# TF_CARD_USB.net
KiCad netlist of a schematic drawn in Altium Designer
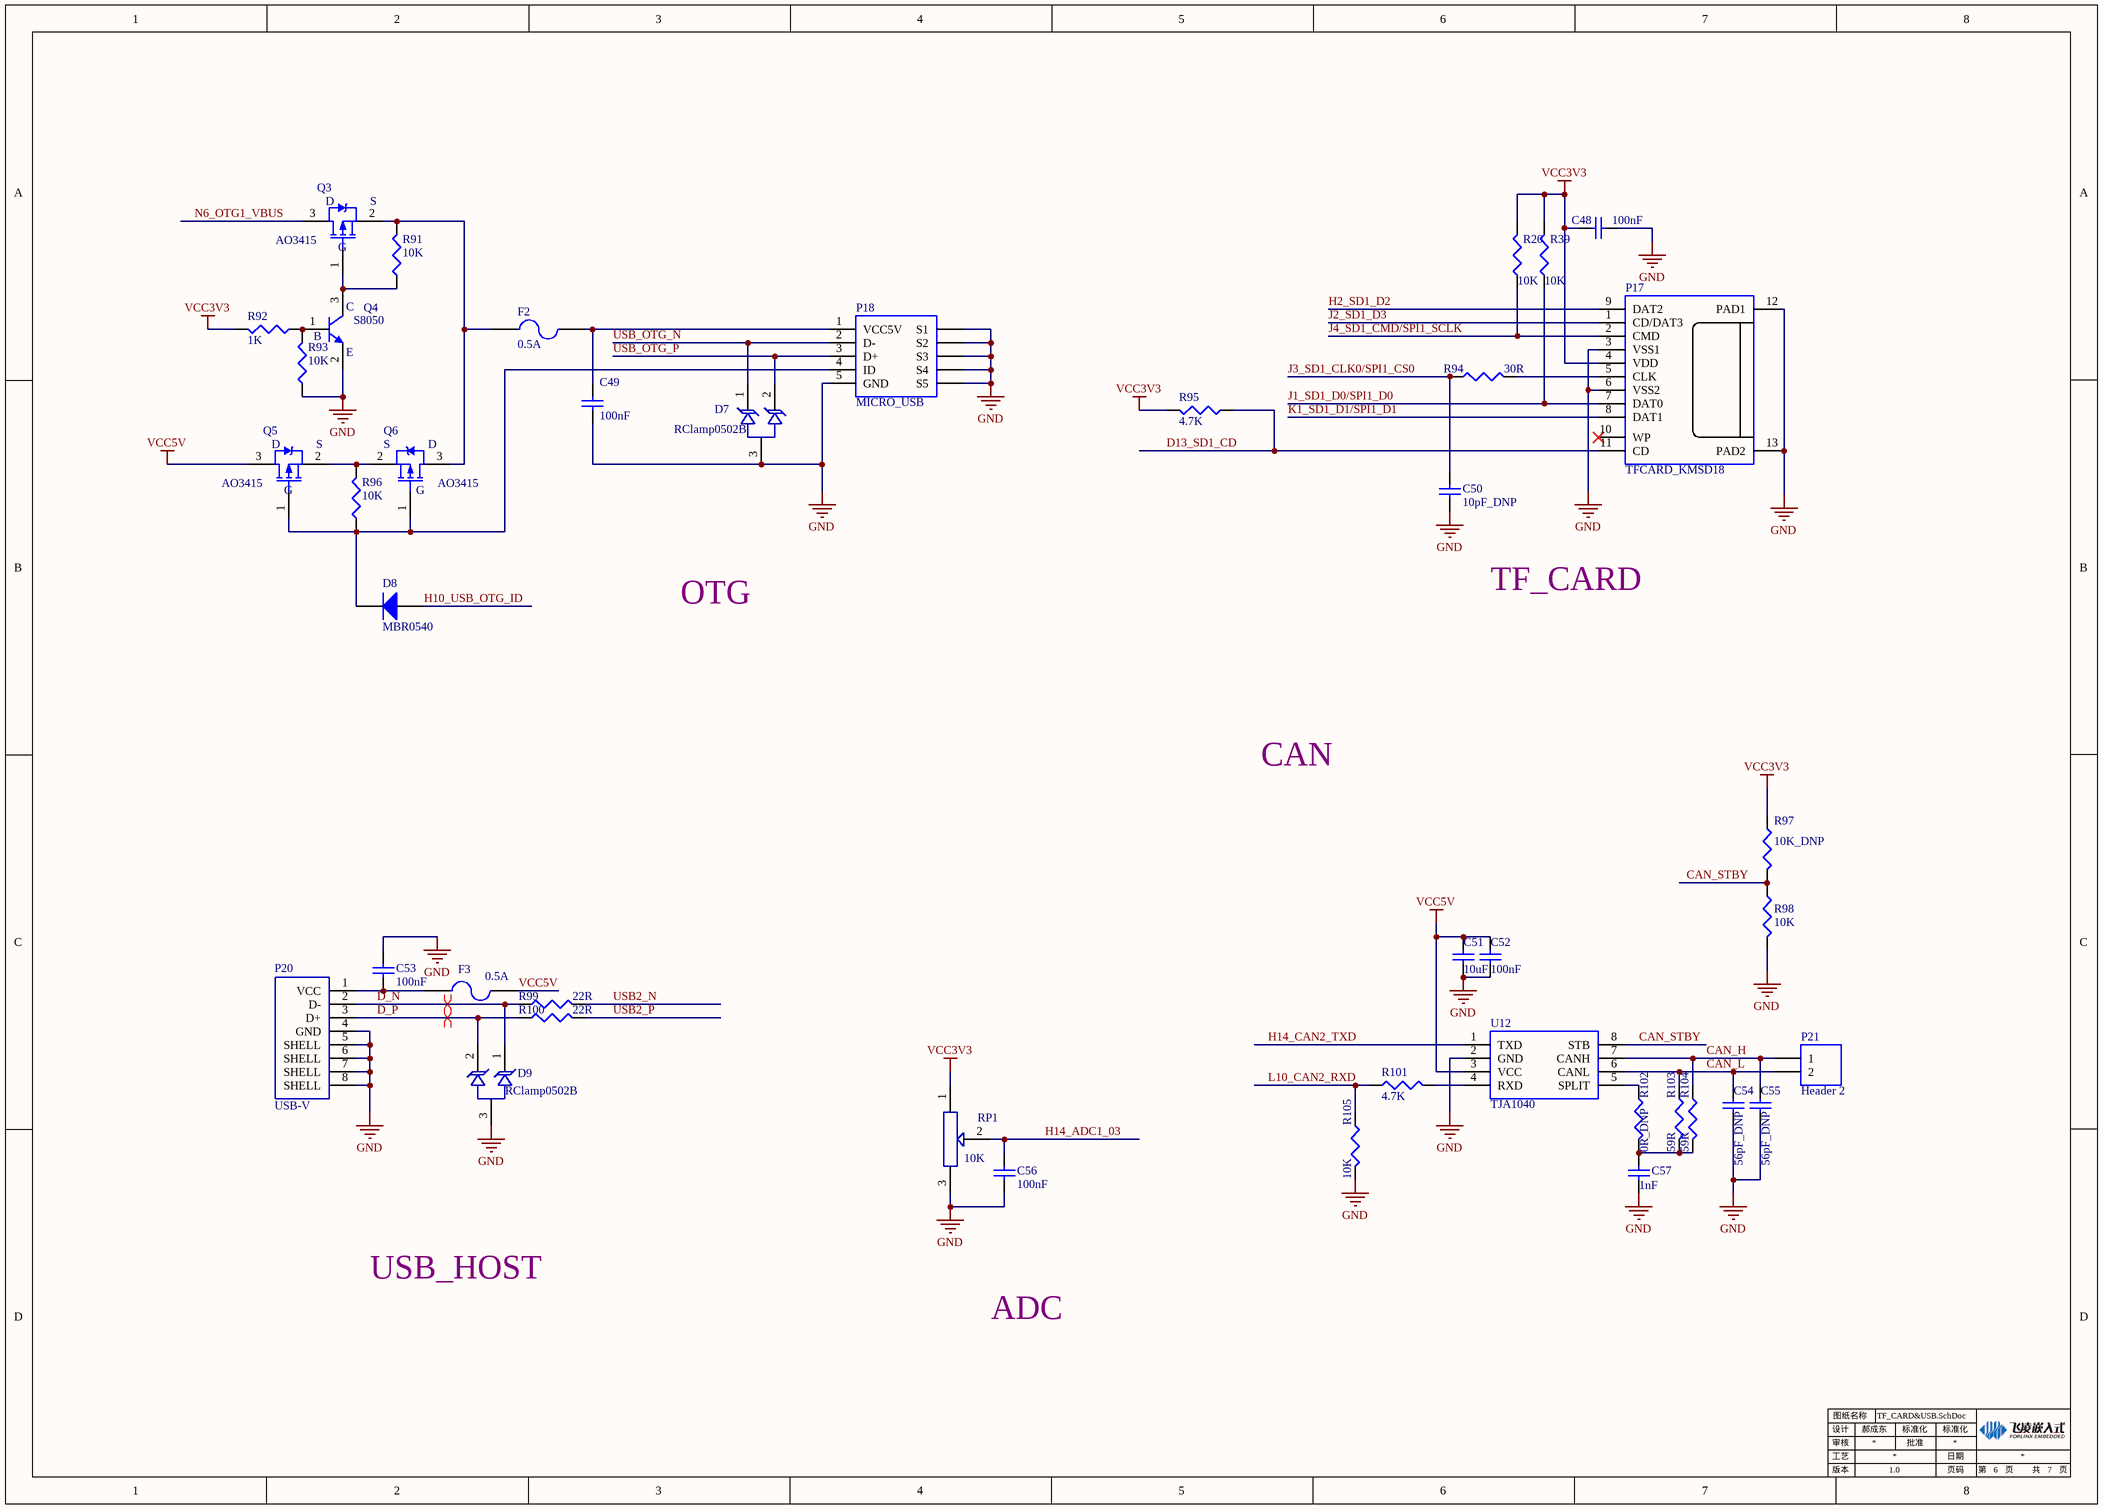
[diagram p0: TF_CARD&USB.SchDoc]

(export (version "E")
  (design (tool "Eeschema 10.0.6"))
  (components
    (comp (ref "C48")
      (value "100nF")
      (footprint "0603C+")
      (description "Capacitor")
      (fields (field (name "PUBLISHER") "Altium Limited"))
      (libsource (lib "Miscellaneous Devices") (part "Cap"))
    )
    (comp (ref "C49")
      (value "100nF")
      (footprint "0603C+")
      (description "Capacitor")
      (fields (field (name "PUBLISHER") "Altium Limited"))
      (libsource (lib "Miscellaneous Devices") (part "Cap"))
    )
    (comp (ref "C50")
      (value "10pF_DNP")
      (footprint "0603C+")
      (description "Capacitor")
      (fields (field (name "PUBLISHER") "Altium Limited"))
      (libsource (lib "Miscellaneous Devices") (part "Cap"))
    )
    (comp (ref "C51")
      (value "10uF")
      (footprint "0603C+")
      (description "Capacitor")
      (fields (field (name "PUBLISHER") "Altium Limited"))
      (libsource (lib "Miscellaneous Devices") (part "Cap"))
    )
    (comp (ref "C52")
      (value "100nF")
      (footprint "0603C+")
      (description "Capacitor")
      (fields (field (name "PUBLISHER") "Altium Limited"))
      (libsource (lib "Miscellaneous Devices") (part "Cap"))
    )
    (comp (ref "C53")
      (value "100nF")
      (footprint "0603C+")
      (description "Capacitor")
      (fields (field (name "PUBLISHER") "Altium Limited"))
      (libsource (lib "Miscellaneous Devices") (part "Cap"))
    )
    (comp (ref "C54")
      (value "56pF_DNP")
      (footprint "0603C+")
      (description "Capacitor")
      (fields (field (name "PUBLISHER") "Altium Limited"))
      (libsource (lib "Miscellaneous Devices") (part "Cap"))
    )
    (comp (ref "C55")
      (value "56pF_DNP")
      (footprint "0603C+")
      (description "Capacitor")
      (fields (field (name "PUBLISHER") "Altium Limited"))
      (libsource (lib "Miscellaneous Devices") (part "Cap"))
    )
    (comp (ref "C56")
      (value "100nF")
      (footprint "0603C+")
      (description "Capacitor")
      (fields (field (name "PUBLISHER") "Altium Limited"))
      (libsource (lib "Miscellaneous Devices") (part "Cap"))
    )
    (comp (ref "C57")
      (value "1nF")
      (footprint "0603C+")
      (description "Capacitor")
      (fields (field (name "PUBLISHER") "Altium Limited"))
      (libsource (lib "Miscellaneous Devices") (part "Cap"))
    )
    (comp (ref "D7") (value "RClamp0502B") (footprint "SOT-523") (libsource (lib "Sch") (part "LCTVS")))
    (comp (ref "D8")
      (value "MBR0540")
      (footprint "Diode1.6*2.6")
      (description "Default Diode")
      (fields (field (name "PUBLISHER") "Altium Limited"))
      (libsource (lib "Miscellaneous Devices") (part "Diode"))
    )
    (comp (ref "D9") (value "RClamp0502B") (footprint "SOT-523") (libsource (lib "Sch") (part "LCTVS")))
    (comp (ref "F2")
      (value "0.5A")
      (footprint "R_1210")
      (description "Fuse")
      (fields (field (name "PUBLISHER") "Altium Limited"))
      (libsource (lib "Miscellaneous Devices") (part "Fuse 2"))
    )
    (comp (ref "F3")
      (value "0.5A")
      (footprint "R_1210")
      (description "Fuse")
      (fields (field (name "PUBLISHER") "Altium Limited"))
      (libsource (lib "Miscellaneous Devices") (part "Fuse 2"))
    )
    (comp (ref "P17")
      (value "TFCARD_KMSD18")
      (footprint "TF-CARD")
      (libsource (lib "IMX6QP") (part "SDCARD_KMSD18"))
    )
    (comp (ref "P18")
      (value "MICRO_USB")
      (footprint "microUSB")
      (description "Header, 5-Pin, Dual row")
      (fields (field (name "PUBLISHER") "Altium Limited"))
      (libsource (lib "PCB_RT1052") (part "MICRO_USB"))
    )
    (comp (ref "P20") (value "USB-V") (footprint "USB-C") (libsource (lib "IMX6QP-C") (part "USB-V")))
    (comp (ref "P21")
      (value "Header 2")
      (footprint "DG128-2P")
      (libsource (lib "PCB_RT1052") (part "Header 2"))
    )
    (comp (ref "Q3")
      (value "AO3415")
      (footprint "SOT95P245X110-3N")
      (description "N-Channel Power MOSFET")
      (fields (field (name "PUBLISHER") "Altium Limited"))
      (libsource (lib "KQX6A") (part "PMOS"))
    )
    (comp (ref "Q4")
      (value "S8050")
      (footprint "SOT95P245X110-3N")
      (description "NPN Bipolar Transistor")
      (fields (field (name "PUBLISHER") "Altium Limited"))
      (libsource (lib "KQX6A") (part "NPN"))
    )
    (comp (ref "Q5")
      (value "AO3415")
      (footprint "SOT95P245X110-3N")
      (description "N-Channel Power MOSFET")
      (fields (field (name "PUBLISHER") "Altium Limited"))
      (libsource (lib "KQX6A") (part "PMOS"))
    )
    (comp (ref "Q6")
      (value "AO3415")
      (footprint "SOT95P245X110-3N")
      (description "N-Channel Power MOSFET")
      (fields (field (name "PUBLISHER") "Altium Limited"))
      (libsource (lib "KQX6A") (part "PMOS"))
    )
    (comp (ref "R20")
      (value "10K")
      (footprint "0603R+")
      (description "Resistor")
      (fields (field (name "PUBLISHER") "Altium Limited"))
      (libsource (lib "") (part "Res3_1"))
    )
    (comp (ref "R39")
      (value "10K")
      (footprint "0603R+")
      (description "Resistor")
      (fields (field (name "PUBLISHER") "Altium Limited"))
      (libsource (lib "") (part "Res3_1"))
    )
    (comp (ref "R91")
      (value "10K")
      (footprint "0603R+")
      (description "Resistor")
      (fields (field (name "PUBLISHER") "Altium Limited"))
      (libsource (lib "") (part "Res3_1"))
    )
    (comp (ref "R92")
      (value "1K")
      (footprint "0603R+")
      (description "Resistor")
      (fields (field (name "PUBLISHER") "Altium Limited"))
      (libsource (lib "") (part "Res3_1"))
    )
    (comp (ref "R93")
      (value "10K")
      (footprint "0603R+")
      (description "Resistor")
      (fields (field (name "PUBLISHER") "Altium Limited"))
      (libsource (lib "") (part "Res3_1"))
    )
    (comp (ref "R94")
      (value "30R")
      (footprint "0603R+")
      (description "Resistor")
      (fields (field (name "PUBLISHER") "Altium Limited"))
      (libsource (lib "") (part "Res3_1"))
    )
    (comp (ref "R95")
      (value "4.7K")
      (footprint "0603R+")
      (description "Resistor")
      (fields (field (name "PUBLISHER") "Altium Limited"))
      (libsource (lib "") (part "Res3_1"))
    )
    (comp (ref "R96")
      (value "10K")
      (footprint "0603R+")
      (description "Resistor")
      (fields (field (name "PUBLISHER") "Altium Limited"))
      (libsource (lib "") (part "Res3_1"))
    )
    (comp (ref "R97")
      (value "10K_DNP")
      (footprint "0603R+")
      (description "Resistor")
      (fields (field (name "PUBLISHER") "Altium Limited"))
      (libsource (lib "Miscellaneous Devices") (part "Res3"))
    )
    (comp (ref "R98")
      (value "10K")
      (footprint "0603R+")
      (description "Resistor")
      (fields (field (name "PUBLISHER") "Altium Limited"))
      (libsource (lib "Miscellaneous Devices") (part "Res3"))
    )
    (comp (ref "R99")
      (value "22R")
      (footprint "0603R+")
      (description "Resistor")
      (fields (field (name "PUBLISHER") "Altium Limited"))
      (libsource (lib "") (part "Res3_1"))
    )
    (comp (ref "R100")
      (value "22R")
      (footprint "0603R+")
      (description "Resistor")
      (fields (field (name "PUBLISHER") "Altium Limited"))
      (libsource (lib "") (part "Res3_1"))
    )
    (comp (ref "R101")
      (value "4.7K")
      (footprint "0603R+")
      (description "Resistor")
      (fields (field (name "PUBLISHER") "Altium Limited"))
      (libsource (lib "Miscellaneous Devices") (part "Res3"))
    )
    (comp (ref "R102")
      (value "0R_DNP")
      (footprint "0603R+")
      (description "Resistor")
      (fields (field (name "PUBLISHER") "Altium Limited"))
      (libsource (lib "Miscellaneous Devices") (part "Res3"))
    )
    (comp (ref "R103")
      (value "59R")
      (footprint "0603R+")
      (description "Resistor")
      (fields (field (name "PUBLISHER") "Altium Limited"))
      (libsource (lib "Miscellaneous Devices") (part "Res3"))
    )
    (comp (ref "R104")
      (value "59R")
      (footprint "0603R+")
      (description "Resistor")
      (fields (field (name "PUBLISHER") "Altium Limited"))
      (libsource (lib "Miscellaneous Devices") (part "Res3"))
    )
    (comp (ref "R105")
      (value "10K")
      (footprint "0603R+")
      (description "Resistor")
      (fields (field (name "PUBLISHER") "Altium Limited"))
      (libsource (lib "Miscellaneous Devices") (part "Res3"))
    )
    (comp (ref "RP1")
      (value "10K")
      (footprint "3296W")
      (fields (field (name "Comment") "VR-3296W"))
      (libsource (lib "Sch") (part "VR"))
    )
    (comp (ref "U12")
      (value "TJA1040")
      (footprint "SOP127P600X175-8N")
      (libsource (lib "IMX6QP") (part "TJA1040"))
    )
  )
  (nets
    (net (code "1") (name "/CAN_H") (class "Default")
      (node (ref "C55") (pin "1") (pinfunction "1_1") (pintype "passive"))
      (node (ref "P21") (pin "1") (pinfunction "1_1") (pintype "passive"))
      (node (ref "R104") (pin "1") (pinfunction "1_1") (pintype "passive"))
      (node (ref "U12") (pin "7") (pinfunction "CANH_7") (pintype "passive"))
    )
    (net (code "2") (name "/CAN_L") (class "Default")
      (node (ref "C54") (pin "1") (pinfunction "1_1") (pintype "passive"))
      (node (ref "P21") (pin "2") (pinfunction "2_2") (pintype "passive"))
      (node (ref "R103") (pin "1") (pinfunction "1_1") (pintype "passive"))
      (node (ref "U12") (pin "6") (pinfunction "CANL_6") (pintype "passive"))
    )
    (net (code "3") (name "/CAN_STBY") (class "Default")
      (node (ref "R97") (pin "2") (pinfunction "2_2") (pintype "passive"))
      (node (ref "R98") (pin "1") (pinfunction "1_1") (pintype "passive"))
      (node (ref "U12") (pin "8") (pinfunction "STB_8") (pintype "passive"))
    )
    (net (code "4") (name "/D13_SD1_CD") (class "Default")
      (node (ref "P17") (pin "11") (pinfunction "CD_11") (pintype "passive"))
      (node (ref "R95") (pin "1") (pinfunction "1_1") (pintype "passive"))
    )
    (net (code "5") (name "/D_N") (class "Default")
      (node (ref "D9") (pin "1") (pinfunction "1_1") (pintype "passive"))
      (node (ref "P20") (pin "2") (pinfunction "D-_2") (pintype "passive"))
      (node (ref "R99") (pin "1") (pinfunction "1_1") (pintype "passive"))
    )
    (net (code "6") (name "/D_P") (class "Default")
      (node (ref "D9") (pin "2") (pinfunction "2_2") (pintype "passive"))
      (node (ref "P20") (pin "3") (pinfunction "D+_3") (pintype "passive"))
      (node (ref "R100") (pin "1") (pinfunction "1_1") (pintype "passive"))
    )
    (net (code "7") (name "/H2_SD1_D2") (class "Default")
      (node (ref "P17") (pin "9") (pinfunction "DAT2_9") (pintype "passive"))
    )
    (net (code "8") (name "/H10_USB_OTG_ID") (class "Default")
      (node (ref "D8") (pin "1") (pinfunction "A_1") (pintype "passive"))
    )
    (net (code "9") (name "/H14_ADC1_03") (class "Default")
      (node (ref "C56") (pin "2") (pinfunction "2_2") (pintype "passive"))
      (node (ref "RP1") (pin "2") (pinfunction "VCC_2") (pintype "passive"))
    )
    (net (code "10") (name "/H14_CAN2_TXD") (class "Default")
      (node (ref "U12") (pin "1") (pinfunction "TXD_1") (pintype "passive"))
    )
    (net (code "11") (name "/J1_SD1_D0{slash}SPI1_D0") (class "Default")
      (node (ref "P17") (pin "7") (pinfunction "DAT0_7") (pintype "passive"))
      (node (ref "R39") (pin "1") (pinfunction "1_1") (pintype "passive"))
    )
    (net (code "12") (name "/J2_SD1_D3") (class "Default")
      (node (ref "P17") (pin "1") (pinfunction "CD/DAT3_1") (pintype "passive"))
    )
    (net (code "13") (name "/J3_SD1_CLK0{slash}SPI1_CS0") (class "Default")
      (node (ref "C50") (pin "1") (pinfunction "1_1") (pintype "passive"))
      (node (ref "R94") (pin "1") (pinfunction "1_1") (pintype "passive"))
    )
    (net (code "14") (name "/J4_SD1_CMD{slash}SPI1_SCLK") (class "Default")
      (node (ref "P17") (pin "2") (pinfunction "CMD_2") (pintype "passive"))
      (node (ref "R20") (pin "1") (pinfunction "1_1") (pintype "passive"))
    )
    (net (code "15") (name "/K1_SD1_D1{slash}SPI1_D1") (class "Default")
      (node (ref "P17") (pin "8") (pinfunction "DAT1_8") (pintype "passive"))
    )
    (net (code "16") (name "/L10_CAN2_RXD") (class "Default")
      (node (ref "R101") (pin "1") (pinfunction "1_1") (pintype "passive"))
      (node (ref "R105") (pin "1") (pinfunction "1_1") (pintype "passive"))
    )
    (net (code "17") (name "/N6_OTG1_VBUS") (class "Default")
      (node (ref "Q3") (pin "3") (pinfunction "D_3") (pintype "passive"))
    )
    (net (code "18") (name "/USB2_N") (class "Default")
      (node (ref "R99") (pin "2") (pinfunction "2_2") (pintype "passive"))
    )
    (net (code "19") (name "/USB2_P") (class "Default")
      (node (ref "R100") (pin "2") (pinfunction "2_2") (pintype "passive"))
    )
    (net (code "20") (name "/USB_OTG_N") (class "Default")
      (node (ref "D7") (pin "1") (pinfunction "1_1") (pintype "passive"))
      (node (ref "P18") (pin "2") (pinfunction "D-_2") (pintype "passive"))
    )
    (net (code "21") (name "/USB_OTG_P") (class "Default")
      (node (ref "D7") (pin "2") (pinfunction "2_2") (pintype "passive"))
      (node (ref "P18") (pin "3") (pinfunction "D+_3") (pintype "passive"))
    )
    (net (code "22") (name "GND") (class "Default")
      (node (ref "C48") (pin "1") (pinfunction "1_1") (pintype "passive"))
      (node (ref "C49") (pin "1") (pinfunction "1_1") (pintype "passive"))
      (node (ref "C50") (pin "2") (pinfunction "2_2") (pintype "passive"))
      (node (ref "C51") (pin "2") (pinfunction "2_2") (pintype "passive"))
      (node (ref "C52") (pin "2") (pinfunction "2_2") (pintype "passive"))
      (node (ref "C53") (pin "1") (pinfunction "1_1") (pintype "passive"))
      (node (ref "C54") (pin "2") (pinfunction "2_2") (pintype "passive"))
      (node (ref "C55") (pin "2") (pinfunction "2_2") (pintype "passive"))
      (node (ref "C56") (pin "1") (pinfunction "1_1") (pintype "passive"))
      (node (ref "C57") (pin "2") (pinfunction "2_2") (pintype "passive"))
      (node (ref "D7") (pin "3") (pintype "passive"))
      (node (ref "D9") (pin "3") (pintype "passive"))
      (node (ref "P17") (pin "12") (pinfunction "PAD1_12") (pintype "passive"))
      (node (ref "P17") (pin "13") (pinfunction "PAD2_13") (pintype "passive"))
      (node (ref "P17") (pin "3") (pinfunction "VSS1_3") (pintype "passive"))
      (node (ref "P17") (pin "6") (pinfunction "VSS2_6") (pintype "passive"))
      (node (ref "P18") (pin "10") (pinfunction "S5_10") (pintype "passive"))
      (node (ref "P18") (pin "5") (pinfunction "GND_5") (pintype "passive"))
      (node (ref "P18") (pin "6") (pinfunction "S1_6") (pintype "passive"))
      (node (ref "P18") (pin "7") (pinfunction "S2_7") (pintype "passive"))
      (node (ref "P18") (pin "8") (pinfunction "S3_8") (pintype "passive"))
      (node (ref "P18") (pin "9") (pinfunction "S4_9") (pintype "passive"))
      (node (ref "P20") (pin "4") (pinfunction "GND_4") (pintype "passive"))
      (node (ref "P20") (pin "5") (pinfunction "SHELL_5") (pintype "passive"))
      (node (ref "P20") (pin "6") (pinfunction "SHELL_6") (pintype "passive"))
      (node (ref "P20") (pin "7") (pinfunction "SHELL_7") (pintype "passive"))
      (node (ref "P20") (pin "8") (pinfunction "SHELL_8") (pintype "passive"))
      (node (ref "Q4") (pin "2") (pinfunction "E_2") (pintype "passive"))
      (node (ref "R105") (pin "2") (pinfunction "2_2") (pintype "passive"))
      (node (ref "R93") (pin "1") (pinfunction "1_1") (pintype "passive"))
      (node (ref "R98") (pin "2") (pinfunction "2_2") (pintype "passive"))
      (node (ref "RP1") (pin "3") (pinfunction "VCC_3") (pintype "passive"))
      (node (ref "U12") (pin "2") (pinfunction "GND_2") (pintype "passive"))
    )
    (net (code "23") (name "Net-(C57-Pad1)") (class "Default")
      (node (ref "C57") (pin "1") (pinfunction "1_1") (pintype "passive"))
      (node (ref "R102") (pin "2") (pinfunction "2_2") (pintype "passive"))
      (node (ref "R103") (pin "2") (pinfunction "2_2") (pintype "passive"))
      (node (ref "R104") (pin "2") (pinfunction "2_2") (pintype "passive"))
    )
    (net (code "24") (name "Net-(D8-K)") (class "Default")
      (node (ref "D8") (pin "2") (pinfunction "K_2") (pintype "passive"))
      (node (ref "P18") (pin "4") (pinfunction "ID_4") (pintype "passive"))
      (node (ref "Q5") (pin "1") (pinfunction "G_1") (pintype "passive"))
      (node (ref "Q6") (pin "1") (pinfunction "G_1") (pintype "passive"))
      (node (ref "R96") (pin "1") (pinfunction "1_1") (pintype "passive"))
    )
    (net (code "25") (name "Net-(P17-CLK)") (class "Default")
      (node (ref "P17") (pin "5") (pinfunction "CLK_5") (pintype "passive"))
      (node (ref "R94") (pin "2") (pinfunction "2_2") (pintype "passive"))
    )
    (net (code "26") (name "Net-(P18-VCC5V)") (class "Default")
      (node (ref "C49") (pin "2") (pinfunction "2_2") (pintype "passive"))
      (node (ref "F2") (pin "1") (pinfunction "1_1") (pintype "passive"))
      (node (ref "P18") (pin "1") (pinfunction "VCC5V_1") (pintype "passive"))
    )
    (net (code "27") (name "Net-(P20-VCC)") (class "Default")
      (node (ref "C53") (pin "2") (pinfunction "2_2") (pintype "passive"))
      (node (ref "F3") (pin "2") (pinfunction "2_2") (pintype "passive"))
      (node (ref "P20") (pin "1") (pinfunction "VCC_1") (pintype "passive"))
    )
    (net (code "28") (name "Net-(Q3-G)") (class "Default")
      (node (ref "Q3") (pin "1") (pinfunction "G_1") (pintype "passive"))
      (node (ref "Q4") (pin "3") (pinfunction "C_3") (pintype "passive"))
      (node (ref "R91") (pin "1") (pinfunction "1_1") (pintype "passive"))
    )
    (net (code "29") (name "Net-(Q3-S)") (class "Default")
      (node (ref "F2") (pin "2") (pinfunction "2_2") (pintype "passive"))
      (node (ref "Q3") (pin "2") (pinfunction "S_2") (pintype "passive"))
      (node (ref "Q6") (pin "3") (pinfunction "D_3") (pintype "passive"))
      (node (ref "R91") (pin "2") (pinfunction "2_2") (pintype "passive"))
    )
    (net (code "30") (name "Net-(Q4-B)") (class "Default")
      (node (ref "Q4") (pin "1") (pinfunction "B_1") (pintype "passive"))
      (node (ref "R92") (pin "1") (pinfunction "1_1") (pintype "passive"))
      (node (ref "R93") (pin "2") (pinfunction "2_2") (pintype "passive"))
    )
    (net (code "31") (name "Net-(Q5-S)") (class "Default")
      (node (ref "Q5") (pin "2") (pinfunction "S_2") (pintype "passive"))
      (node (ref "Q6") (pin "2") (pinfunction "S_2") (pintype "passive"))
      (node (ref "R96") (pin "2") (pinfunction "2_2") (pintype "passive"))
    )
    (net (code "32") (name "Net-(U12-RXD)") (class "Default")
      (node (ref "R101") (pin "2") (pinfunction "2_2") (pintype "passive"))
      (node (ref "U12") (pin "4") (pinfunction "RXD_4") (pintype "passive"))
    )
    (net (code "33") (name "Net-(U12-SPLIT)") (class "Default")
      (node (ref "R102") (pin "1") (pinfunction "1_1") (pintype "passive"))
      (node (ref "U12") (pin "5") (pinfunction "SPLIT_5") (pintype "passive"))
    )
    (net (code "34") (name "VCC3V3") (class "Default")
      (node (ref "C48") (pin "2") (pinfunction "2_2") (pintype "passive"))
      (node (ref "P17") (pin "4") (pinfunction "VDD_4") (pintype "passive"))
      (node (ref "R20") (pin "2") (pinfunction "2_2") (pintype "passive"))
      (node (ref "R39") (pin "2") (pinfunction "2_2") (pintype "passive"))
      (node (ref "R92") (pin "2") (pinfunction "2_2") (pintype "passive"))
      (node (ref "R95") (pin "2") (pinfunction "2_2") (pintype "passive"))
      (node (ref "R97") (pin "1") (pinfunction "1_1") (pintype "passive"))
      (node (ref "RP1") (pin "1") (pinfunction "VCC_1") (pintype "passive"))
    )
    (net (code "35") (name "VCC5V") (class "Default")
      (node (ref "C51") (pin "1") (pinfunction "1_1") (pintype "passive"))
      (node (ref "C52") (pin "1") (pinfunction "1_1") (pintype "passive"))
      (node (ref "F3") (pin "1") (pinfunction "1_1") (pintype "passive"))
      (node (ref "Q5") (pin "3") (pinfunction "D_3") (pintype "passive"))
      (node (ref "U12") (pin "3") (pinfunction "VCC_3") (pintype "passive"))
    )
    (net (code "36") (name "unconnected-(P17-WP-Pad10)") (class "Default")
      (node (ref "P17") (pin "10") (pinfunction "WP_10") (pintype "passive+no_connect"))
    )
  )
)
